# CH32V003-NFC-EVT-R0-1v0.net
KiCad netlist of a schematic drawn in Altium Designer
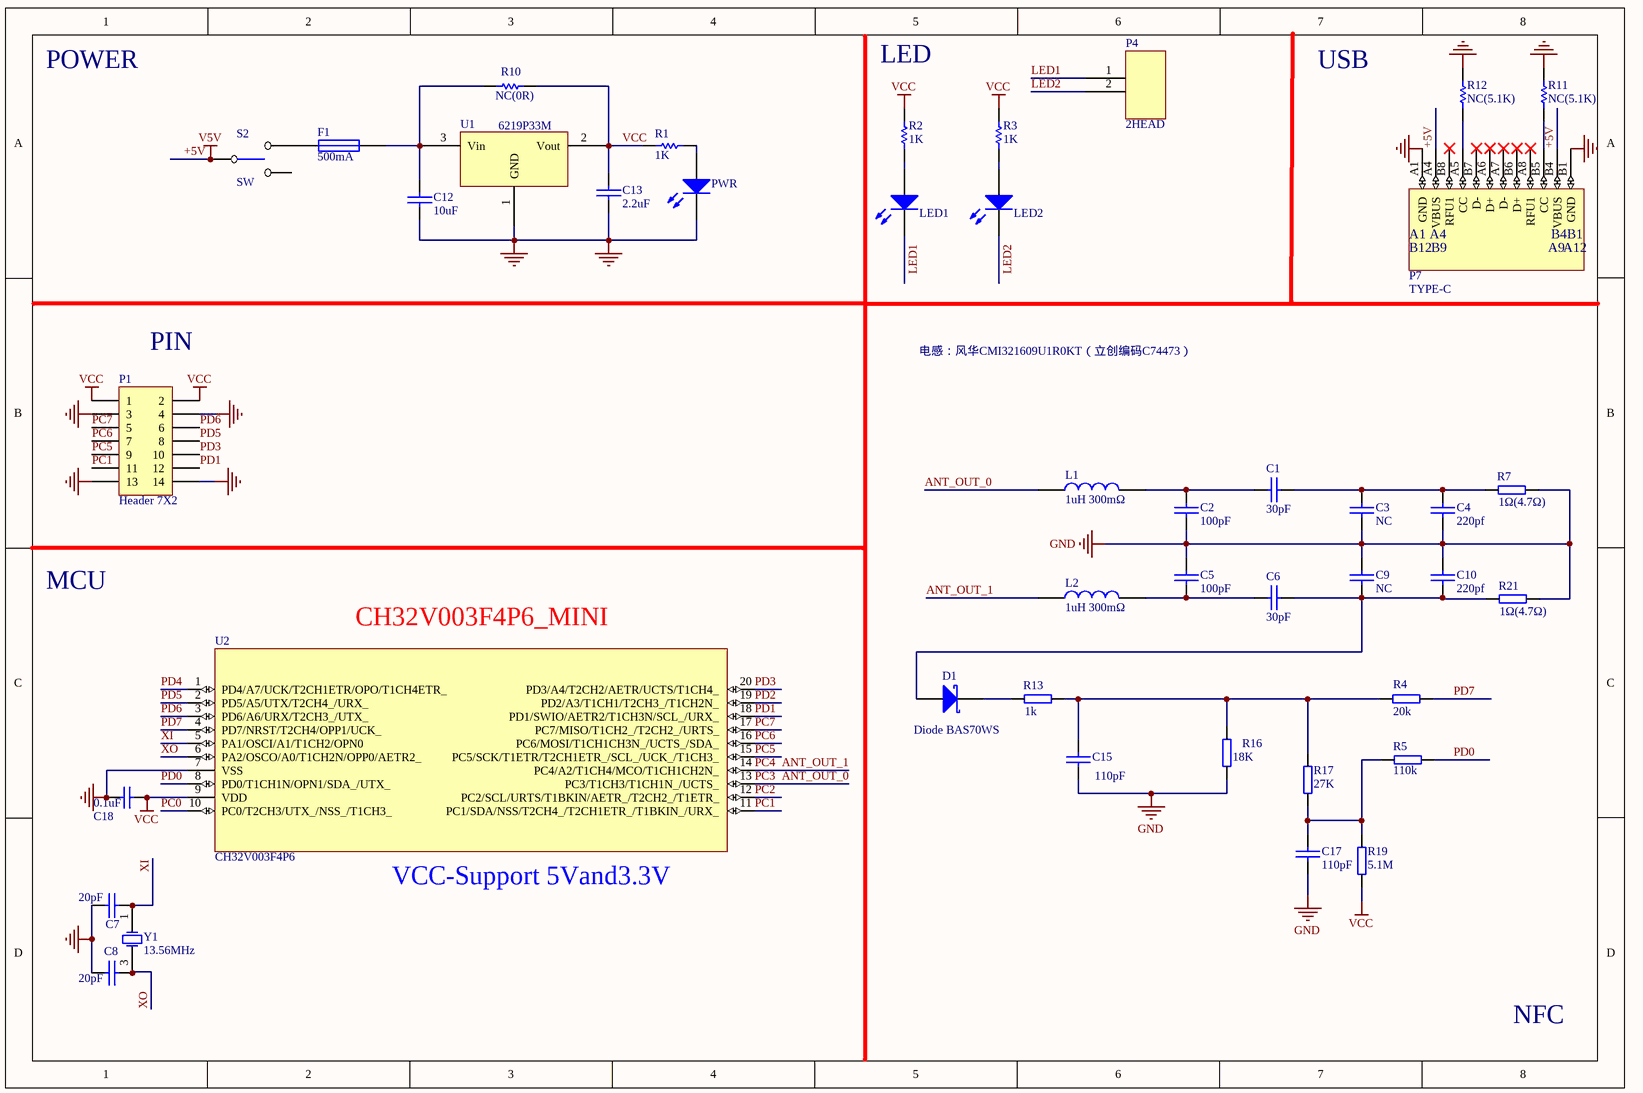
[diagram p0: CH32V003-NFC-EVT-R0-1v0.SchDoc]

(export (version "E")
  (design (tool "Eeschema 10.0.6"))
  (components
    (comp (ref "C1")
      (value "30pF")
      (footprint "0603_C")
      (description "Capacitor")
      (libsource (lib "wch_sch_others") (part "CAP"))
    )
    (comp (ref "C2")
      (value "100pF")
      (footprint "0603_C")
      (description "Capacitor")
      (libsource (lib "wch_sch_others") (part "CAP"))
    )
    (comp (ref "C3")
      (value "NC")
      (footprint "0603_C")
      (description "Capacitor")
      (libsource (lib "wch_sch_others") (part "CAP"))
    )
    (comp (ref "C4")
      (value "220pf")
      (footprint "0603_C")
      (description "Capacitor")
      (libsource (lib "wch_sch_others") (part "CAP"))
    )
    (comp (ref "C5")
      (value "100pF")
      (footprint "0603_C")
      (description "Capacitor")
      (libsource (lib "wch_sch_others") (part "CAP"))
    )
    (comp (ref "C6")
      (value "30pF")
      (footprint "0603_C")
      (description "Capacitor")
      (libsource (lib "wch_sch_others") (part "CAP"))
    )
    (comp (ref "C7")
      (value "20pF")
      (footprint "0603_C")
      (description "Capacitor")
      (libsource (lib "*") (part "CAP"))
    )
    (comp (ref "C8")
      (value "20pF")
      (footprint "0603_C")
      (description "Capacitor")
      (libsource (lib "*") (part "CAP"))
    )
    (comp (ref "C9")
      (value "NC")
      (footprint "0603_C")
      (description "Capacitor")
      (libsource (lib "wch_sch_others") (part "CAP"))
    )
    (comp (ref "C10")
      (value "220pf")
      (footprint "0603_C")
      (description "Capacitor")
      (libsource (lib "wch_sch_others") (part "CAP"))
    )
    (comp (ref "C12")
      (value "10uF")
      (footprint "3216_C")
      (description "Capacitor")
      (libsource (lib "wch_sch_others") (part "CAP"))
    )
    (comp (ref "C13")
      (value "2.2uF")
      (footprint "0603_C")
      (description "Capacitor")
      (libsource (lib "wch_sch_others") (part "CAP"))
    )
    (comp (ref "C15")
      (value "110pF")
      (footprint "0603_C")
      (description "Capacitor")
      (libsource (lib "wch_sch_others") (part "CAP"))
    )
    (comp (ref "C17")
      (value "110pF")
      (footprint "0603_C")
      (description "Capacitor")
      (libsource (lib "wch_sch_others") (part "CAP"))
    )
    (comp (ref "C18")
      (value "0.1uF")
      (footprint "0603_C")
      (description "Capacitor")
      (fields (field (name "PUBLISHER") "Altium Limited"))
      (libsource (lib "*") (part "Cap"))
    )
    (comp (ref "D1")
      (value "Diode BAS70WS")
      (footprint "SOD-323")
      (description "Silicon AF Schottky Diode for High-Speed Switching")
      (fields (field (name "PUBLISHER") "Altium Limited"))
      (libsource (lib "Miscellaneous Devices") (part "Diode BAS70"))
    )
    (comp (ref "F1")
      (value "500mA")
      (footprint "0603")
      (description "Fuse")
      (libsource (lib "*") (part "FUSE1"))
    )
    (comp (ref "L1") (value "1uH 300mΩ") (footprint "0805") (libsource (lib "*") (part "INDUCTOR")))
    (comp (ref "L2") (value "1uH 300mΩ") (footprint "0805") (libsource (lib "*") (part "INDUCTOR")))
    (comp (ref "LED1")
      (value "LED1   blue")
      (footprint "0603+")
      (description "Typical INFRARED GaAs LED")
      (fields (field (name "PUBLISHER") "Altium Limited"))
      (libsource (lib "*") (part "LED0"))
    )
    (comp (ref "LED2")
      (value "LED2  blue")
      (footprint "0603+")
      (description "Typical INFRARED GaAs LED")
      (fields (field (name "PUBLISHER") "Altium Limited"))
      (libsource (lib "*") (part "LED0"))
    )
    (comp (ref "P1")
      (value "Header 7X2")
      (footprint "IDC14-2.54mm")
      (description "Header, 7-Pin, Dual row")
      (fields (field (name "PUBLISHER") "Altium Limited"))
      (libsource (lib "Miscellaneous Connectors") (part "Header 7X2"))
    )
    (comp (ref "P4") (value "2HEAD") (footprint "SIP2-2.54mm") (libsource (lib "*") (part "2HEAD")))
    (comp (ref "P7")
      (value "TYPE-C")
      (footprint "TYPE-C-Receptacle-2.0")
      (libsource (lib "*") (part "TYPE-C1"))
    )
    (comp (ref "PWR")
      (value "POWER  red")
      (footprint "0603+")
      (description "Typical INFRARED GaAs LED")
      (fields (field (name "PUBLISHER") "Altium Limited"))
      (libsource (lib "") (part "LED0_1"))
    )
    (comp (ref "R1")
      (value "1K")
      (footprint "0603")
      (description "Semiconductor Resistor")
      (fields (field (name "PUBLISHER") "Altium Limited"))
      (libsource (lib "*") (part "Res Semi"))
    )
    (comp (ref "R2")
      (value "1K")
      (footprint "0603")
      (description "Semiconductor Resistor")
      (fields (field (name "PUBLISHER") "Altium Limited"))
      (libsource (lib "*") (part "Res Semi"))
    )
    (comp (ref "R3")
      (value "1K")
      (footprint "0603")
      (description "Semiconductor Resistor")
      (fields (field (name "PUBLISHER") "Altium Limited"))
      (libsource (lib "*") (part "Res Semi"))
    )
    (comp (ref "R4") (value "20k") (footprint "0603") (libsource (lib "wch_sch_others") (part "RES")))
    (comp (ref "R5") (value "110k") (footprint "0603") (libsource (lib "wch_sch_others") (part "RES")))
    (comp (ref "R7") (value "1Ω(4.7Ω)") (footprint "0603") (libsource (lib "wch_sch_others") (part "RES")))
    (comp (ref "R10")
      (value "NC(0R)")
      (footprint "0603")
      (description "Semiconductor Resistor")
      (fields (field (name "Comment") "0R") (field (name "PUBLISHER") "Altium Limited"))
      (libsource (lib "*") (part "Res Semi"))
    )
    (comp (ref "R11")
      (value "NC(5.1K)")
      (footprint "0603")
      (description "Semiconductor Resistor")
      (fields (field (name "Comment") "0R") (field (name "PUBLISHER") "Altium Limited"))
      (libsource (lib "*") (part "Res Semi"))
    )
    (comp (ref "R12")
      (value "NC(5.1K)")
      (footprint "0603")
      (description "Semiconductor Resistor")
      (fields (field (name "Comment") "0R") (field (name "PUBLISHER") "Altium Limited"))
      (libsource (lib "*") (part "Res Semi"))
    )
    (comp (ref "R13") (value "1k") (footprint "0603") (libsource (lib "wch_sch_others") (part "RES")))
    (comp (ref "R16") (value "18K") (footprint "0603") (libsource (lib "wch_sch_others") (part "RES")))
    (comp (ref "R17") (value "27K") (footprint "0603") (libsource (lib "wch_sch_others") (part "RES")))
    (comp (ref "R19") (value "5.1M") (footprint "0603") (libsource (lib "wch_sch_others") (part "RES")))
    (comp (ref "R21") (value "1Ω(4.7Ω)") (footprint "0603") (libsource (lib "wch_sch_others") (part "RES")))
    (comp (ref "S2") (value "SW") (footprint "SW1") (libsource (lib "*") (part "SW")))
    (comp (ref "U1")
      (value "6219P33M")
      (footprint "SOT-23")
      (libsource (lib "wch_sch_others") (part "6219P33M"))
    )
    (comp (ref "U2")
      (value "CH32V003F4P6")
      (footprint "TSSOP20")
      (description "RISC-V MCU, 48MHz")
      (libsource (lib "CHXXX") (part "CH32V003F4P6"))
    )
    (comp (ref "Y1")
      (value "13.56MHz")
      (footprint "XT3225")
      (description "Crystal Oscillator")
      (fields (field (name "PUBLISHER") "Altium Limited"))
      (libsource (lib "*") (part "XTAL"))
    )
  )
  (nets
    (net (code "1") (name "/ANT_OUT_0") (class "Default")
      (node (ref "L1") (pin "1") (pinfunction "1_1") (pintype "passive"))
      (node (ref "U2") (pin "13") (pinfunction "PC3/T1CH3/T1CH1N_/UCTS__13") (pintype "bidirectional"))
    )
    (net (code "2") (name "/ANT_OUT_1") (class "Default")
      (node (ref "L2") (pin "1") (pinfunction "1_1") (pintype "passive"))
      (node (ref "U2") (pin "14") (pinfunction "PC4/A2/T1CH4/MCO/T1CH1CH2N__14") (pintype "bidirectional"))
    )
    (net (code "3") (name "/LED1") (class "Default")
      (node (ref "LED1") (pin "2") (pinfunction "K_2") (pintype "passive"))
      (node (ref "P4") (pin "1") (pintype "passive"))
    )
    (net (code "4") (name "/LED2") (class "Default")
      (node (ref "LED2") (pin "2") (pinfunction "K_2") (pintype "passive"))
      (node (ref "P4") (pin "2") (pintype "passive"))
    )
    (net (code "5") (name "/PC0") (class "Default")
      (node (ref "U2") (pin "10") (pinfunction "PC0/T2CH3/UTX_/NSS_/T1CH3__10") (pintype "bidirectional"))
    )
    (net (code "6") (name "/PC1") (class "Default")
      (node (ref "P1") (pin "11") (pinfunction "11_11") (pintype "passive"))
      (node (ref "U2") (pin "11") (pinfunction "PC1/SDA/NSS/T2CH4_/T2CH1ETR_/T1BKIN_/URX__11") (pintype "bidirectional"))
    )
    (net (code "7") (name "/PC2") (class "Default")
      (node (ref "U2") (pin "12") (pinfunction "PC2/SCL/URTS/T1BKIN/AETR_/T2CH2_/T1ETR__12") (pintype "bidirectional"))
    )
    (net (code "8") (name "/PC5") (class "Default")
      (node (ref "P1") (pin "9") (pinfunction "9_9") (pintype "passive"))
      (node (ref "U2") (pin "15") (pinfunction "PC5/SCK/T1ETR/T2CH1ETR_/SCL_/UCK_/T1CH3__15") (pintype "bidirectional"))
    )
    (net (code "9") (name "/PC6") (class "Default")
      (node (ref "P1") (pin "7") (pinfunction "7_7") (pintype "passive"))
      (node (ref "U2") (pin "16") (pinfunction "PC6/MOSI/T1CH1CH3N_/UCTS_/SDA__16") (pintype "bidirectional"))
    )
    (net (code "10") (name "/PC7") (class "Default")
      (node (ref "P1") (pin "5") (pinfunction "5_5") (pintype "passive"))
      (node (ref "U2") (pin "17") (pinfunction "PC7/MISO/T1CH2_/T2CH2_/URTS__17") (pintype "bidirectional"))
    )
    (net (code "11") (name "/PD0") (class "Default")
      (node (ref "R5") (pin "2") (pintype "passive"))
      (node (ref "U2") (pin "8") (pinfunction "PD0/T1CH1N/OPN1/SDA_/UTX__8") (pintype "bidirectional"))
    )
    (net (code "12") (name "/PD1") (class "Default")
      (node (ref "P1") (pin "12") (pinfunction "12_12") (pintype "passive"))
      (node (ref "U2") (pin "18") (pinfunction "PD1/SWIO/AETR2/T1CH3N/SCL_/URX__18") (pintype "bidirectional"))
    )
    (net (code "13") (name "/PD2") (class "Default")
      (node (ref "U2") (pin "19") (pinfunction "PD2/A3/T1CH1/T2CH3_/T1CH2N__19") (pintype "bidirectional"))
    )
    (net (code "14") (name "/PD3") (class "Default")
      (node (ref "P1") (pin "10") (pinfunction "10_10") (pintype "passive"))
      (node (ref "U2") (pin "20") (pinfunction "PD3/A4/T2CH2/AETR/UCTS/T1CH4__20") (pintype "bidirectional"))
    )
    (net (code "15") (name "/PD4") (class "Default")
      (node (ref "U2") (pin "1") (pinfunction "PD4/A7/UCK/T2CH1ETR/OPO/T1CH4ETR__1") (pintype "bidirectional"))
    )
    (net (code "16") (name "/PD5") (class "Default")
      (node (ref "P1") (pin "8") (pinfunction "8_8") (pintype "passive"))
      (node (ref "U2") (pin "2") (pinfunction "PD5/A5/UTX/T2CH4_/URX__2") (pintype "bidirectional"))
    )
    (net (code "17") (name "/PD6") (class "Default")
      (node (ref "P1") (pin "6") (pinfunction "6_6") (pintype "passive"))
      (node (ref "U2") (pin "3") (pinfunction "PD6/A6/URX/T2CH3_/UTX__3") (pintype "bidirectional"))
    )
    (net (code "18") (name "/PD7") (class "Default")
      (node (ref "R4") (pin "1") (pintype "passive"))
      (node (ref "U2") (pin "4") (pinfunction "PD7/NRST/T2CH4/OPP1/UCK__4") (pintype "bidirectional"))
    )
    (net (code "19") (name "/XI") (class "Default")
      (node (ref "C7") (pin "2") (pinfunction "2_2") (pintype "passive"))
      (node (ref "U2") (pin "5") (pinfunction "PA1/OSCI/A1/T1CH2/OPN0_5") (pintype "bidirectional"))
      (node (ref "Y1") (pin "1") (pinfunction "OSC1_1") (pintype "passive"))
    )
    (net (code "20") (name "/XO") (class "Default")
      (node (ref "C8") (pin "2") (pinfunction "2_2") (pintype "passive"))
      (node (ref "U2") (pin "6") (pinfunction "PA2/OSCO/A0/T1CH2N/OPP0/AETR2__6") (pintype "bidirectional"))
      (node (ref "Y1") (pin "3") (pinfunction "OSC2_3") (pintype "passive"))
    )
    (net (code "21") (name "GND") (class "Default")
      (node (ref "C10") (pin "2") (pinfunction "2_2") (pintype "passive"))
      (node (ref "C12") (pin "2") (pinfunction "2_2") (pintype "passive"))
      (node (ref "C13") (pin "1") (pinfunction "1_1") (pintype "passive"))
      (node (ref "C15") (pin "1") (pinfunction "1_1") (pintype "passive"))
      (node (ref "C17") (pin "1") (pinfunction "1_1") (pintype "passive"))
      (node (ref "C18") (pin "1") (pinfunction "1_1") (pintype "passive"))
      (node (ref "C2") (pin "1") (pinfunction "1_1") (pintype "passive"))
      (node (ref "C3") (pin "1") (pinfunction "1_1") (pintype "passive"))
      (node (ref "C4") (pin "1") (pinfunction "1_1") (pintype "passive"))
      (node (ref "C5") (pin "2") (pinfunction "2_2") (pintype "passive"))
      (node (ref "C7") (pin "1") (pinfunction "1_1") (pintype "passive"))
      (node (ref "C8") (pin "1") (pinfunction "1_1") (pintype "passive"))
      (node (ref "C9") (pin "2") (pinfunction "2_2") (pintype "passive"))
      (node (ref "P1") (pin "13") (pinfunction "13_13") (pintype "passive"))
      (node (ref "P1") (pin "14") (pinfunction "14_14") (pintype "passive"))
      (node (ref "P1") (pin "3") (pinfunction "3_3") (pintype "passive"))
      (node (ref "P1") (pin "4") (pinfunction "4_4") (pintype "passive"))
      (node (ref "P7") (pin "A1") (pinfunction "GND_A1") (pintype "bidirectional"))
      (node (ref "P7") (pin "B1") (pinfunction "GND_B1") (pintype "bidirectional"))
      (node (ref "PWR") (pin "2") (pinfunction "K_2") (pintype "passive"))
      (node (ref "R11") (pin "2") (pinfunction "2_2") (pintype "passive"))
      (node (ref "R12") (pin "2") (pinfunction "2_2") (pintype "passive"))
      (node (ref "R16") (pin "1") (pintype "passive"))
      (node (ref "R21") (pin "2") (pintype "passive"))
      (node (ref "R7") (pin "2") (pintype "passive"))
      (node (ref "U1") (pin "1") (pinfunction "GND_1") (pintype "passive"))
      (node (ref "U2") (pin "7") (pinfunction "VSS_7") (pintype "power_in"))
    )
    (net (code "22") (name "Net-(C1-Pad1)") (class "Default")
      (node (ref "C1") (pin "1") (pinfunction "1_1") (pintype "passive"))
      (node (ref "C2") (pin "2") (pinfunction "2_2") (pintype "passive"))
      (node (ref "L1") (pin "2") (pinfunction "2_2") (pintype "passive"))
    )
    (net (code "23") (name "Net-(C1-Pad2)") (class "Default")
      (node (ref "C1") (pin "2") (pinfunction "2_2") (pintype "passive"))
      (node (ref "C3") (pin "2") (pinfunction "2_2") (pintype "passive"))
      (node (ref "C4") (pin "2") (pinfunction "2_2") (pintype "passive"))
      (node (ref "R7") (pin "1") (pintype "passive"))
    )
    (net (code "24") (name "Net-(C5-Pad1)") (class "Default")
      (node (ref "C5") (pin "1") (pinfunction "1_1") (pintype "passive"))
      (node (ref "C6") (pin "1") (pinfunction "1_1") (pintype "passive"))
      (node (ref "L2") (pin "2") (pinfunction "2_2") (pintype "passive"))
    )
    (net (code "25") (name "Net-(C15-Pad2)") (class "Default")
      (node (ref "C15") (pin "2") (pinfunction "2_2") (pintype "passive"))
      (node (ref "R13") (pin "2") (pintype "passive"))
      (node (ref "R16") (pin "2") (pintype "passive"))
      (node (ref "R17") (pin "2") (pintype "passive"))
      (node (ref "R4") (pin "2") (pintype "passive"))
    )
    (net (code "26") (name "Net-(C17-Pad2)") (class "Default")
      (node (ref "C17") (pin "2") (pinfunction "2_2") (pintype "passive"))
      (node (ref "R17") (pin "1") (pintype "passive"))
      (node (ref "R19") (pin "2") (pintype "passive"))
      (node (ref "R5") (pin "1") (pintype "passive"))
    )
    (net (code "27") (name "Net-(D1-A)") (class "Default")
      (node (ref "C10") (pin "1") (pinfunction "1_1") (pintype "passive"))
      (node (ref "C6") (pin "2") (pinfunction "2_2") (pintype "passive"))
      (node (ref "C9") (pin "1") (pinfunction "1_1") (pintype "passive"))
      (node (ref "D1") (pin "1") (pinfunction "A_1") (pintype "passive"))
      (node (ref "R21") (pin "1") (pintype "passive"))
    )
    (net (code "28") (name "Net-(D1-K)") (class "Default")
      (node (ref "D1") (pin "2") (pinfunction "K_2") (pintype "passive"))
      (node (ref "R13") (pin "1") (pintype "passive"))
    )
    (net (code "29") (name "Net-(F1-Pad1)") (class "Default")
      (node (ref "F1") (pin "1") (pinfunction "1_1") (pintype "passive"))
      (node (ref "S2") (pin "3") (pinfunction "3_3") (pintype "passive"))
    )
    (net (code "30") (name "Net-(LED1-A)") (class "Default")
      (node (ref "LED1") (pin "1") (pinfunction "A_1") (pintype "passive"))
      (node (ref "R2") (pin "2") (pinfunction "2_2") (pintype "passive"))
    )
    (net (code "31") (name "Net-(LED2-A)") (class "Default")
      (node (ref "LED2") (pin "1") (pinfunction "A_1") (pintype "passive"))
      (node (ref "R3") (pin "2") (pinfunction "2_2") (pintype "passive"))
    )
    (net (code "32") (name "Net-(P7-CC-PadA5)") (class "Default")
      (node (ref "P7") (pin "A5") (pinfunction "CC_A5") (pintype "bidirectional"))
      (node (ref "R12") (pin "1") (pinfunction "1_1") (pintype "passive"))
    )
    (net (code "33") (name "Net-(P7-CC-PadB5)") (class "Default")
      (node (ref "P7") (pin "B5") (pinfunction "CC_B5") (pintype "bidirectional"))
      (node (ref "R11") (pin "1") (pinfunction "1_1") (pintype "passive"))
    )
    (net (code "34") (name "Net-(PWR-A)") (class "Default")
      (node (ref "PWR") (pin "1") (pinfunction "A_1") (pintype "passive"))
      (node (ref "R1") (pin "1") (pinfunction "1_1") (pintype "passive"))
    )
    (net (code "35") (name "Net-(U1-Vin)") (class "Default")
      (node (ref "C12") (pin "1") (pinfunction "1_1") (pintype "passive"))
      (node (ref "F1") (pin "2") (pinfunction "2_2") (pintype "passive"))
      (node (ref "R10") (pin "1") (pinfunction "1_1") (pintype "passive"))
      (node (ref "U1") (pin "3") (pinfunction "Vin_3") (pintype "passive"))
    )
    (net (code "36") (name "V5V") (class "Default")
      (node (ref "P7") (pin "A4") (pinfunction "VBUS_A4") (pintype "bidirectional"))
      (node (ref "P7") (pin "B4") (pinfunction "VBUS_B4") (pintype "bidirectional"))
      (node (ref "S2") (pin "1") (pinfunction "1_1") (pintype "passive"))
    )
    (net (code "37") (name "VCC") (class "Default")
      (node (ref "C13") (pin "2") (pinfunction "2_2") (pintype "passive"))
      (node (ref "C18") (pin "2") (pinfunction "2_2") (pintype "passive"))
      (node (ref "P1") (pin "1") (pinfunction "1_1") (pintype "passive"))
      (node (ref "P1") (pin "2") (pinfunction "2_2") (pintype "passive"))
      (node (ref "R1") (pin "2") (pinfunction "2_2") (pintype "passive"))
      (node (ref "R10") (pin "2") (pinfunction "2_2") (pintype "passive"))
      (node (ref "R19") (pin "1") (pintype "passive"))
      (node (ref "R2") (pin "1") (pinfunction "1_1") (pintype "passive"))
      (node (ref "R3") (pin "1") (pinfunction "1_1") (pintype "passive"))
      (node (ref "U1") (pin "2") (pinfunction "Vout_2") (pintype "passive"))
      (node (ref "U2") (pin "9") (pinfunction "VDD_9") (pintype "power_in"))
    )
    (net (code "38") (name "unconnected-(P7-D+-PadA6)") (class "Default")
      (node (ref "P7") (pin "A6") (pinfunction "D+_A6") (pintype "bidirectional+no_connect"))
    )
    (net (code "39") (name "unconnected-(P7-D+-PadB6)") (class "Default")
      (node (ref "P7") (pin "B6") (pinfunction "D+_B6") (pintype "bidirectional+no_connect"))
    )
    (net (code "40") (name "unconnected-(P7-D--PadA7)") (class "Default")
      (node (ref "P7") (pin "A7") (pinfunction "D-_A7") (pintype "bidirectional+no_connect"))
    )
    (net (code "41") (name "unconnected-(P7-D--PadB7)") (class "Default")
      (node (ref "P7") (pin "B7") (pinfunction "D-_B7") (pintype "bidirectional+no_connect"))
    )
    (net (code "42") (name "unconnected-(P7-RFU1-PadA8)") (class "Default")
      (node (ref "P7") (pin "A8") (pinfunction "RFU1_A8") (pintype "bidirectional+no_connect"))
    )
    (net (code "43") (name "unconnected-(P7-RFU1-PadB8)") (class "Default")
      (node (ref "P7") (pin "B8") (pinfunction "RFU1_B8") (pintype "bidirectional+no_connect"))
    )
    (net (code "44") (name "unconnected-(S2-Pad2)") (class "Default")
      (node (ref "S2") (pin "2") (pinfunction "2_2") (pintype "passive"))
    )
  )
)
